# 150227_AriloTX_REV2_4_0_868MHZ.net
KiCad netlist of a schematic drawn in EAGLE
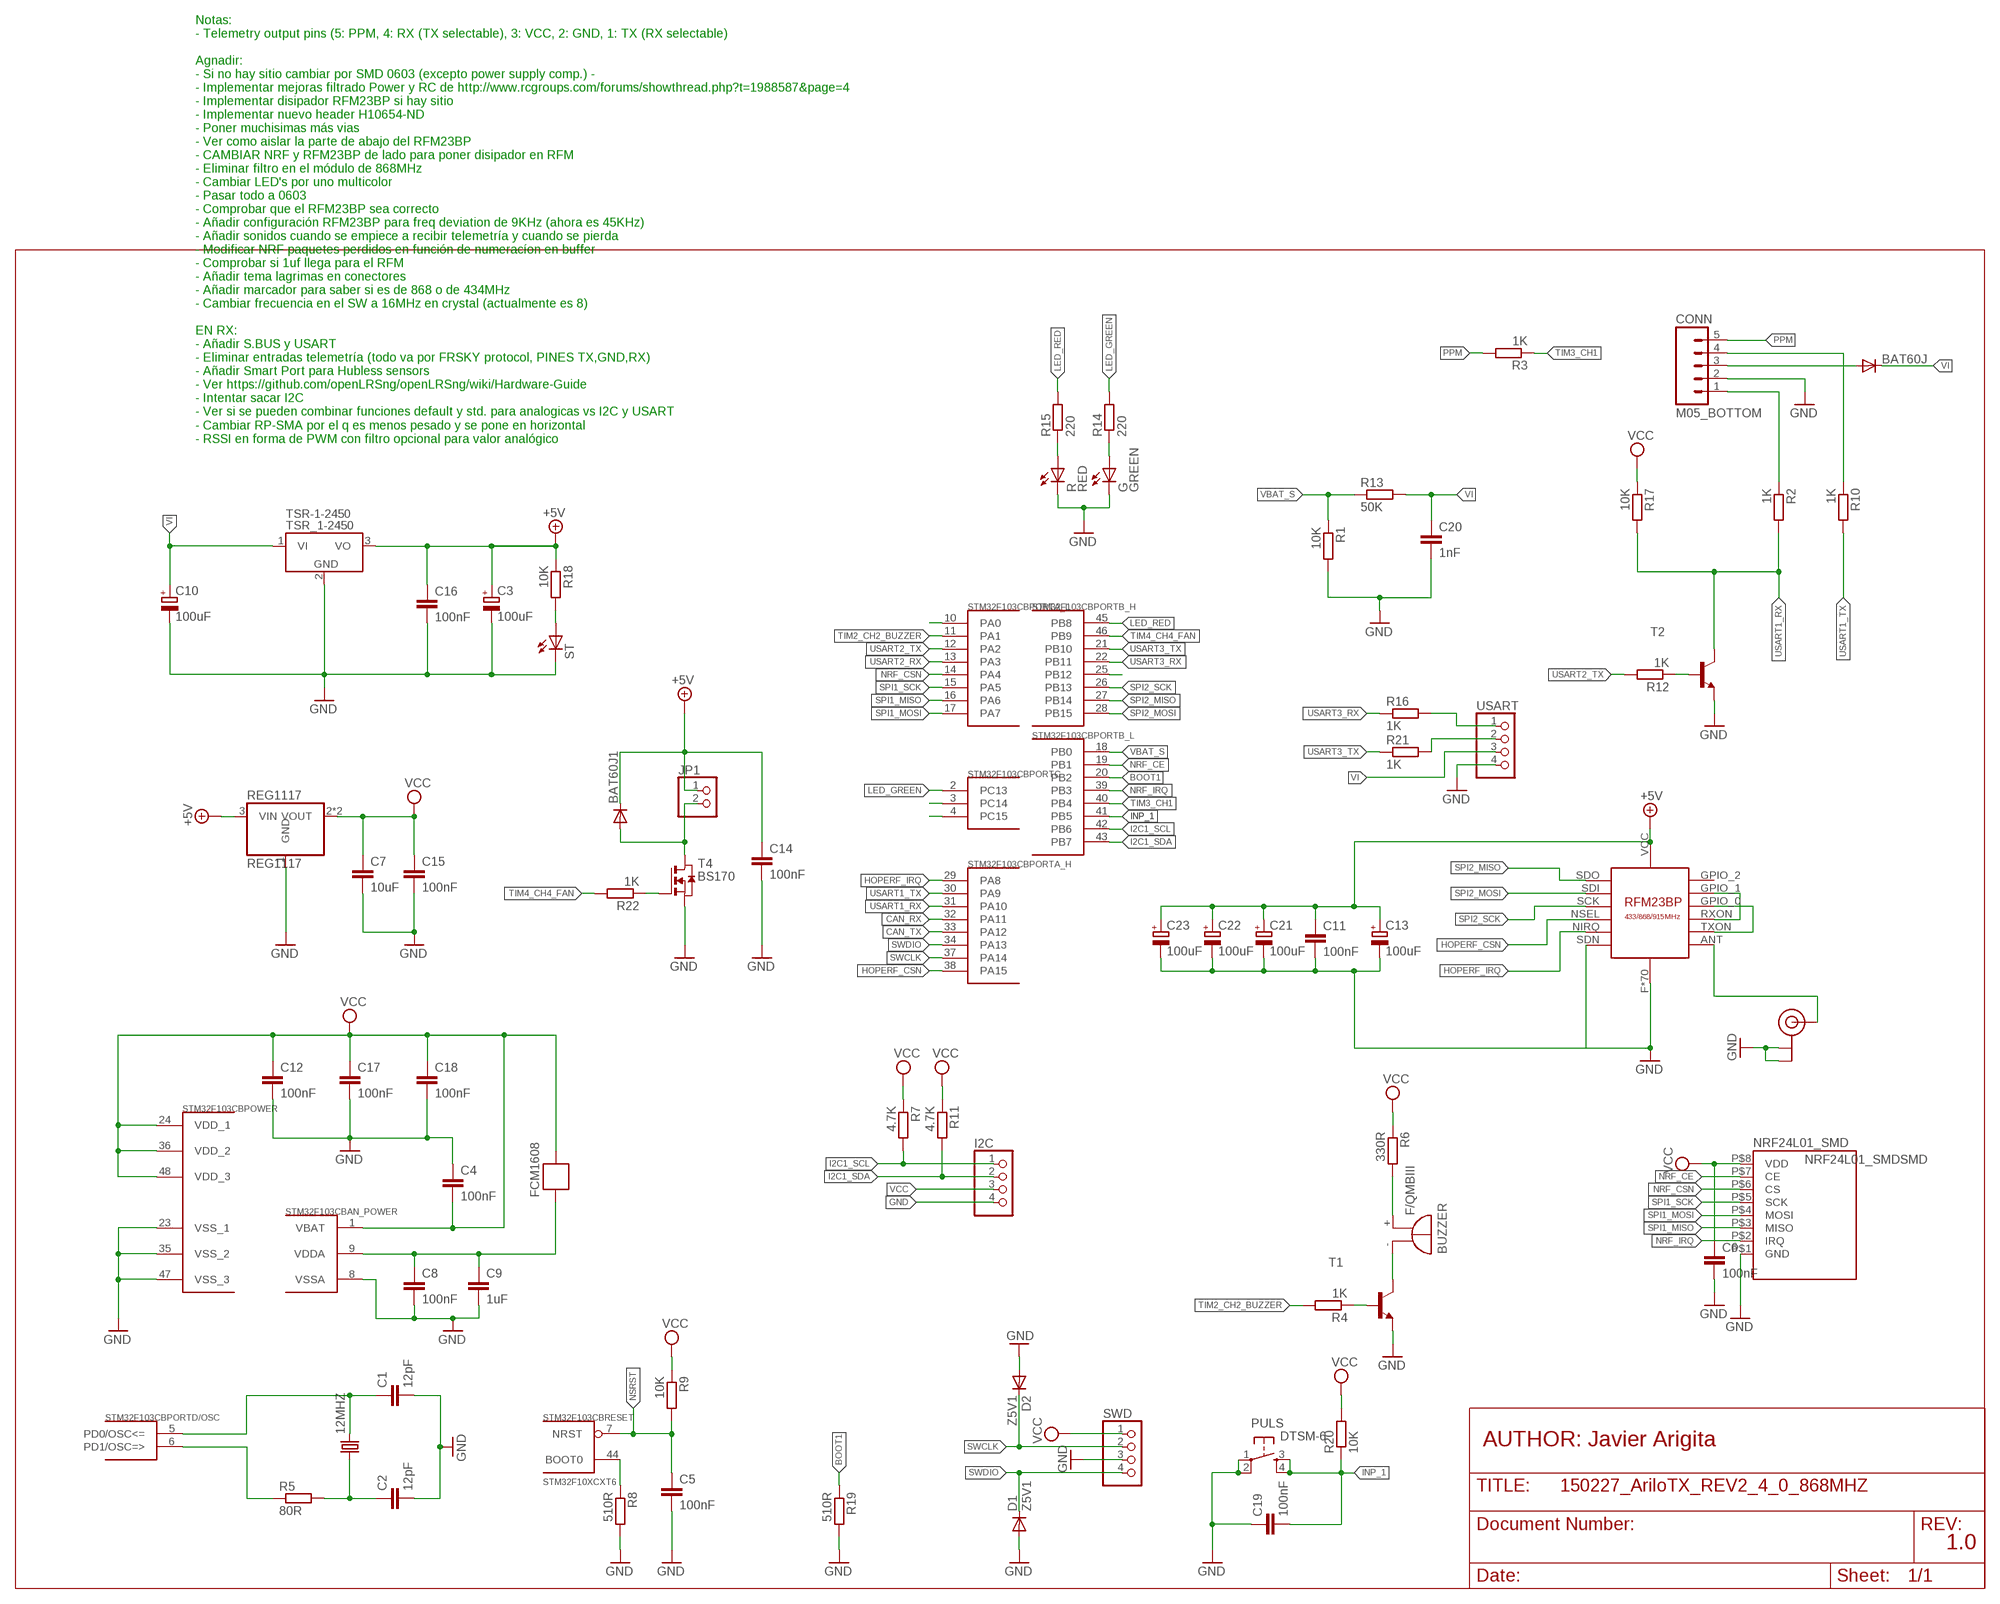
[diagram p0: schematic, sheet 1]

(export (version "E")
  (design (tool "Eeschema 10.0.6"))
  (components
    (comp (ref "12MHZ")
      (value "CRYSTAL5X3")
      (footprint "eagle-import:CRYSTAL-SMD-5X3")
      (libsource (lib "eagle-import") (part "CRYSTAL5X3"))
    )
    (comp (ref "BAT60J")
      (value "DIODE-SOD323-R")
      (footprint "eagle-import:SOD323-R")
      (libsource (lib "eagle-import") (part "DIODE-SOD323-R"))
    )
    (comp (ref "BAT60J1")
      (value "DIODE-SOD323-R")
      (footprint "eagle-import:SOD323-R")
      (libsource (lib "eagle-import") (part "DIODE-SOD323-R"))
    )
    (comp (ref "BUZZER")
      (value "F/QMBIII")
      (footprint "eagle-import:F_QMBIII")
      (libsource (lib "eagle-import") (part "F/QMBIII"))
    )
    (comp (ref "C1")
      (value "12pF")
      (footprint "eagle-import:C0603")
      (libsource (lib "eagle-import") (part "C-EUC0603"))
    )
    (comp (ref "C2")
      (value "12pF")
      (footprint "eagle-import:C0603")
      (libsource (lib "eagle-import") (part "C-EUC0603"))
    )
    (comp (ref "C3")
      (value "100uF")
      (footprint "eagle-import:SMC_B")
      (libsource (lib "eagle-import") (part "CPOL-EUSMCB"))
    )
    (comp (ref "C4")
      (value "100nF")
      (footprint "eagle-import:C0603")
      (libsource (lib "eagle-import") (part "C-EUC0603"))
    )
    (comp (ref "C5")
      (value "100nF")
      (footprint "eagle-import:C0603")
      (libsource (lib "eagle-import") (part "C-EUC0603"))
    )
    (comp (ref "C6")
      (value "100nF")
      (footprint "eagle-import:C0603")
      (libsource (lib "eagle-import") (part "C-EUC0603"))
    )
    (comp (ref "C7")
      (value "10uF")
      (footprint "eagle-import:C0805")
      (libsource (lib "eagle-import") (part "C-EUC0805"))
    )
    (comp (ref "C8")
      (value "100nF")
      (footprint "eagle-import:C0603")
      (libsource (lib "eagle-import") (part "C-EUC0603"))
    )
    (comp (ref "C9")
      (value "1uF")
      (footprint "eagle-import:C0603")
      (libsource (lib "eagle-import") (part "C-EUC0603"))
    )
    (comp (ref "C10")
      (value "100uF")
      (footprint "eagle-import:SMC_B")
      (libsource (lib "eagle-import") (part "CPOL-EUSMCB"))
    )
    (comp (ref "C11")
      (value "100nF")
      (footprint "eagle-import:C0603")
      (libsource (lib "eagle-import") (part "C-EUC0603"))
    )
    (comp (ref "C12")
      (value "100nF")
      (footprint "eagle-import:C0603")
      (libsource (lib "eagle-import") (part "C-EUC0603"))
    )
    (comp (ref "C13")
      (value "100uF")
      (footprint "eagle-import:SMC_B")
      (libsource (lib "eagle-import") (part "CPOL-EUSMCB"))
    )
    (comp (ref "C14")
      (value "100nF")
      (footprint "eagle-import:C0603")
      (libsource (lib "eagle-import") (part "C-EUC0603"))
    )
    (comp (ref "C15")
      (value "100nF")
      (footprint "eagle-import:C0603")
      (libsource (lib "eagle-import") (part "C-EUC0603"))
    )
    (comp (ref "C16")
      (value "100nF")
      (footprint "eagle-import:C0603")
      (libsource (lib "eagle-import") (part "C-EUC0603"))
    )
    (comp (ref "C17")
      (value "100nF")
      (footprint "eagle-import:C0603")
      (libsource (lib "eagle-import") (part "C-EUC0603"))
    )
    (comp (ref "C18")
      (value "100nF")
      (footprint "eagle-import:C0603")
      (libsource (lib "eagle-import") (part "C-EUC0603"))
    )
    (comp (ref "C19")
      (value "100nF")
      (footprint "eagle-import:C0603")
      (libsource (lib "eagle-import") (part "C-EUC0603"))
    )
    (comp (ref "C20")
      (value "1nF")
      (footprint "eagle-import:C0603")
      (libsource (lib "eagle-import") (part "C-EUC0603"))
    )
    (comp (ref "C21")
      (value "100uF")
      (footprint "eagle-import:SMC_B")
      (libsource (lib "eagle-import") (part "CPOL-EUSMCB"))
    )
    (comp (ref "C22")
      (value "100uF")
      (footprint "eagle-import:SMC_B")
      (libsource (lib "eagle-import") (part "CPOL-EUSMCB"))
    )
    (comp (ref "C23")
      (value "100uF")
      (footprint "eagle-import:SMC_B")
      (libsource (lib "eagle-import") (part "CPOL-EUSMCB"))
    )
    (comp (ref "CONN")
      (value "M05_BOTTOM")
      (footprint "eagle-import:M05_BOTTOM")
      (libsource (lib "eagle-import") (part "M05_BOTTOM"))
    )
    (comp (ref "D1")
      (value "Z5V1")
      (footprint "eagle-import:SOD323-R")
      (libsource (lib "eagle-import") (part "DIODE-SOD323-R"))
    )
    (comp (ref "D2")
      (value "Z5V1")
      (footprint "eagle-import:SOD323-R")
      (libsource (lib "eagle-import") (part "DIODE-SOD323-R"))
    )
    (comp (ref "FCM1608")
      (value "FERRITE-BEAD")
      (footprint "eagle-import:R0603")
      (libsource (lib "eagle-import") (part "FERRITE-BEAD"))
    )
    (comp (ref "G")
      (value "GREEN")
      (footprint "eagle-import:CHIP-LED0603")
      (libsource (lib "eagle-import") (part "LEDCHIP-LED0603"))
    )
    (comp (ref "I2C")
      (value "PINHD-1X4")
      (footprint "eagle-import:1X04")
      (libsource (lib "eagle-import") (part "PINHD-1X4"))
    )
    (comp (ref "JP1")
      (value "PINHD-1X2")
      (footprint "eagle-import:1X02")
      (libsource (lib "eagle-import") (part "PINHD-1X2"))
    )
    (comp (ref "NRF24L01_SMD")
      (value "NRF24L01_SMDSMD")
      (footprint "eagle-import:NRF24L01_SMD")
      (libsource (lib "eagle-import") (part "NRF24L01_SMDSMD"))
    )
    (comp (ref "PULS")
      (value "DTSM-6")
      (footprint "eagle-import:DTSM-6")
      (libsource (lib "eagle-import") (part "DTSM-6"))
    )
    (comp (ref "R")
      (value "RED")
      (footprint "eagle-import:CHIP-LED0603")
      (libsource (lib "eagle-import") (part "LEDCHIP-LED0603"))
    )
    (comp (ref "R1")
      (value "10K")
      (footprint "eagle-import:R0603")
      (libsource (lib "eagle-import") (part "R-EU_R0603"))
    )
    (comp (ref "R2")
      (value "1K")
      (footprint "eagle-import:R0603")
      (libsource (lib "eagle-import") (part "R-EU_R0603"))
    )
    (comp (ref "R3")
      (value "1K")
      (footprint "eagle-import:R0603")
      (libsource (lib "eagle-import") (part "R-EU_R0603"))
    )
    (comp (ref "R4")
      (value "1K")
      (footprint "eagle-import:R0603")
      (libsource (lib "eagle-import") (part "R-EU_R0603"))
    )
    (comp (ref "R5")
      (value "80R")
      (footprint "eagle-import:R0603")
      (libsource (lib "eagle-import") (part "R-EU_R0603"))
    )
    (comp (ref "R6")
      (value "330R")
      (footprint "eagle-import:R0603")
      (libsource (lib "eagle-import") (part "R-EU_R0603"))
    )
    (comp (ref "R7")
      (value "4.7K")
      (footprint "eagle-import:R0603")
      (libsource (lib "eagle-import") (part "R-EU_R0603"))
    )
    (comp (ref "R8")
      (value "510R")
      (footprint "eagle-import:R0603")
      (libsource (lib "eagle-import") (part "R-EU_R0603"))
    )
    (comp (ref "R9")
      (value "10K")
      (footprint "eagle-import:R0603")
      (libsource (lib "eagle-import") (part "R-EU_R0603"))
    )
    (comp (ref "R10")
      (value "1K")
      (footprint "eagle-import:R0603")
      (libsource (lib "eagle-import") (part "R-EU_R0603"))
    )
    (comp (ref "R11")
      (value "4.7K")
      (footprint "eagle-import:R0603")
      (libsource (lib "eagle-import") (part "R-EU_R0603"))
    )
    (comp (ref "R12")
      (value "1K")
      (footprint "eagle-import:R0603")
      (libsource (lib "eagle-import") (part "R-EU_R0603"))
    )
    (comp (ref "R13")
      (value "50K")
      (footprint "eagle-import:R0603")
      (libsource (lib "eagle-import") (part "R-EU_R0603"))
    )
    (comp (ref "R14")
      (value "220")
      (footprint "eagle-import:R0603")
      (libsource (lib "eagle-import") (part "R-EU_R0603"))
    )
    (comp (ref "R15")
      (value "220")
      (footprint "eagle-import:R0603")
      (libsource (lib "eagle-import") (part "R-EU_R0603"))
    )
    (comp (ref "R16")
      (value "1K")
      (footprint "eagle-import:R0603")
      (libsource (lib "eagle-import") (part "R-EU_R0603"))
    )
    (comp (ref "R17")
      (value "10K")
      (footprint "eagle-import:R0603")
      (libsource (lib "eagle-import") (part "R-EU_R0603"))
    )
    (comp (ref "R18")
      (value "10K")
      (footprint "eagle-import:R0603")
      (libsource (lib "eagle-import") (part "R-EU_R0603"))
    )
    (comp (ref "R19")
      (value "510R")
      (footprint "eagle-import:R0603")
      (libsource (lib "eagle-import") (part "R-EU_R0603"))
    )
    (comp (ref "R20")
      (value "10K")
      (footprint "eagle-import:R0603")
      (libsource (lib "eagle-import") (part "R-EU_R0603"))
    )
    (comp (ref "R21")
      (value "1K")
      (footprint "eagle-import:R0603")
      (libsource (lib "eagle-import") (part "R-EU_R0603"))
    )
    (comp (ref "R22")
      (value "1K")
      (footprint "eagle-import:R0603")
      (libsource (lib "eagle-import") (part "R-EU_R0603"))
    )
    (comp (ref "REG1117")
      (value "REG1117")
      (footprint "eagle-import:SOT223")
      (libsource (lib "eagle-import") (part "REG1117"))
    )
    (comp (ref "ST")
      (value "LEDCHIP-LED0603")
      (footprint "eagle-import:CHIP-LED0603")
      (libsource (lib "eagle-import") (part "LEDCHIP-LED0603"))
    )
    (comp (ref "STM32F103CB")
      (value "STM32F10XCXT6")
      (footprint "eagle-import:TQFP48")
      (libsource (lib "eagle-import") (part "STM32F10XCXT6"))
    )
    (comp (ref "SWD")
      (value "PINHD-1X4")
      (footprint "eagle-import:1X04")
      (libsource (lib "eagle-import") (part "PINHD-1X4"))
    )
    (comp (ref "T1")
      (value "BC848-NPN-SOT23-BEC")
      (footprint "eagle-import:SOT23-BEC")
      (libsource (lib "eagle-import") (part "-NPN-SOT23-BECBC848"))
    )
    (comp (ref "T2")
      (value "BC848-NPN-SOT23-BEC")
      (footprint "eagle-import:SOT23-BEC")
      (libsource (lib "eagle-import") (part "-NPN-SOT23-BECBC848"))
    )
    (comp (ref "T4")
      (value "BS170")
      (footprint "eagle-import:SOT-23")
      (libsource (lib "eagle-import") (part "NMOSSOT23"))
    )
    (comp (ref "TSR-1-2450")
      (value "TSR_1-2450")
      (footprint "eagle-import:TSR-1")
      (libsource (lib "eagle-import") (part "TSR_1-2450"))
    )
    (comp (ref "U$1")
      (value "RFM23BP")
      (footprint "eagle-import:RFM23BP")
      (libsource (lib "eagle-import") (part "RFM23BP"))
    )
    (comp (ref "U.FL")
      (value "U.FL")
      (footprint "eagle-import:U.FL")
      (libsource (lib "eagle-import") (part "U.FL"))
    )
    (comp (ref "USART")
      (value "PINHD-1X4")
      (footprint "eagle-import:1X04")
      (libsource (lib "eagle-import") (part "PINHD-1X4"))
    )
  )
  (nets
    (net (code "1") (name "+5V") (class "Default")
      (node (ref "BAT60J1") (pin "C") (pinfunction "C_C") (pintype "passive"))
      (node (ref "C11") (pin "1") (pinfunction "1_1") (pintype "passive"))
      (node (ref "C13") (pin "+") (pinfunction "+_+") (pintype "passive"))
      (node (ref "C14") (pin "1") (pinfunction "1_1") (pintype "passive"))
      (node (ref "C16") (pin "1") (pinfunction "1_1") (pintype "passive"))
      (node (ref "C21") (pin "+") (pinfunction "+_+") (pintype "passive"))
      (node (ref "C22") (pin "+") (pinfunction "+_+") (pintype "passive"))
      (node (ref "C23") (pin "+") (pinfunction "+_+") (pintype "passive"))
      (node (ref "C3") (pin "+") (pinfunction "+_+") (pintype "passive"))
      (node (ref "JP1") (pin "1") (pinfunction "1_1") (pintype "passive"))
      (node (ref "R18") (pin "1") (pinfunction "1_1") (pintype "passive"))
      (node (ref "REG1117") (pin "3") (pinfunction "VIN_3") (pintype "input"))
      (node (ref "TSR-1-2450") (pin "3") (pinfunction "VO_3") (pintype "power_in"))
      (node (ref "U$1") (pin "VCC") (pinfunction "VCC_VCC") (pintype "power_in"))
    )
    (net (code "2") (name "BOOT1") (class "Default")
      (node (ref "R19") (pin "1") (pinfunction "1_1") (pintype "passive"))
      (node (ref "STM32F103CB") (pin "20") (pinfunction "PB2_20") (pintype "bidirectional"))
    )
    (net (code "3") (name "CAN_RX") (class "Default")
      (node (ref "STM32F103CB") (pin "32") (pinfunction "PA11_32") (pintype "bidirectional"))
    )
    (net (code "4") (name "CAN_TX") (class "Default")
      (node (ref "STM32F103CB") (pin "33") (pinfunction "PA12_33") (pintype "bidirectional"))
    )
    (net (code "5") (name "GND") (class "Default")
      (node (ref "C1") (pin "2") (pinfunction "2_2") (pintype "passive"))
      (node (ref "C10") (pin "-") (pinfunction "-_-") (pintype "passive"))
      (node (ref "C11") (pin "2") (pinfunction "2_2") (pintype "passive"))
      (node (ref "C12") (pin "2") (pinfunction "2_2") (pintype "passive"))
      (node (ref "C13") (pin "-") (pinfunction "-_-") (pintype "passive"))
      (node (ref "C14") (pin "2") (pinfunction "2_2") (pintype "passive"))
      (node (ref "C15") (pin "2") (pinfunction "2_2") (pintype "passive"))
      (node (ref "C16") (pin "2") (pinfunction "2_2") (pintype "passive"))
      (node (ref "C17") (pin "2") (pinfunction "2_2") (pintype "passive"))
      (node (ref "C18") (pin "2") (pinfunction "2_2") (pintype "passive"))
      (node (ref "C19") (pin "1") (pinfunction "1_1") (pintype "passive"))
      (node (ref "C2") (pin "2") (pinfunction "2_2") (pintype "passive"))
      (node (ref "C20") (pin "2") (pinfunction "2_2") (pintype "passive"))
      (node (ref "C21") (pin "-") (pinfunction "-_-") (pintype "passive"))
      (node (ref "C22") (pin "-") (pinfunction "-_-") (pintype "passive"))
      (node (ref "C23") (pin "-") (pinfunction "-_-") (pintype "passive"))
      (node (ref "C3") (pin "-") (pinfunction "-_-") (pintype "passive"))
      (node (ref "C4") (pin "1") (pinfunction "1_1") (pintype "passive"))
      (node (ref "C5") (pin "2") (pinfunction "2_2") (pintype "passive"))
      (node (ref "C6") (pin "2") (pinfunction "2_2") (pintype "passive"))
      (node (ref "C7") (pin "2") (pinfunction "2_2") (pintype "passive"))
      (node (ref "C8") (pin "2") (pinfunction "2_2") (pintype "passive"))
      (node (ref "C9") (pin "2") (pinfunction "2_2") (pintype "passive"))
      (node (ref "CONN") (pin "2") (pinfunction "2_2") (pintype "passive"))
      (node (ref "D1") (pin "A") (pinfunction "A_A") (pintype "passive"))
      (node (ref "D2") (pin "A") (pinfunction "A_A") (pintype "passive"))
      (node (ref "G") (pin "C") (pinfunction "C_C") (pintype "passive"))
      (node (ref "I2C") (pin "4") (pinfunction "4_4") (pintype "passive"))
      (node (ref "NRF24L01_SMD") (pin "P$1") (pinfunction "GND_P$1") (pintype "power_in"))
      (node (ref "PULS") (pin "1") (pinfunction "1_1") (pintype "passive"))
      (node (ref "PULS") (pin "2") (pinfunction "2_2") (pintype "passive"))
      (node (ref "R") (pin "C") (pinfunction "C_C") (pintype "passive"))
      (node (ref "R1") (pin "2") (pinfunction "2_2") (pintype "passive"))
      (node (ref "R19") (pin "2") (pinfunction "2_2") (pintype "passive"))
      (node (ref "R8") (pin "2") (pinfunction "2_2") (pintype "passive"))
      (node (ref "REG1117") (pin "1") (pinfunction "GND_1") (pintype "power_in"))
      (node (ref "ST") (pin "C") (pinfunction "C_C") (pintype "passive"))
      (node (ref "STM32F103CB") (pin "23") (pinfunction "VSS_1_23") (pintype "power_in"))
      (node (ref "STM32F103CB") (pin "35") (pinfunction "VSS_2_35") (pintype "power_in"))
      (node (ref "STM32F103CB") (pin "47") (pinfunction "VSS_3_47") (pintype "power_in"))
      (node (ref "STM32F103CB") (pin "8") (pinfunction "VSSA_8") (pintype "power_in"))
      (node (ref "SWD") (pin "3") (pinfunction "3_3") (pintype "passive"))
      (node (ref "T1") (pin "E") (pinfunction "E_E") (pintype "passive"))
      (node (ref "T2") (pin "E") (pinfunction "E_E") (pintype "passive"))
      (node (ref "T4") (pin "2") (pinfunction "S_2") (pintype "passive"))
      (node (ref "TSR-1-2450") (pin "2") (pinfunction "GND_2") (pintype "power_in"))
      (node (ref "U$1") (pin "F") (pinfunction "GND_F") (pintype "power_in"))
      (node (ref "U$1") (pin "F1") (pinfunction "GND_F1") (pintype "power_in"))
      (node (ref "U$1") (pin "F10") (pinfunction "GND_F10") (pintype "power_in"))
      (node (ref "U$1") (pin "F11") (pinfunction "GND_F11") (pintype "power_in"))
      (node (ref "U$1") (pin "F12") (pinfunction "GND_F12") (pintype "power_in"))
      (node (ref "U$1") (pin "F13") (pinfunction "GND_F13") (pintype "power_in"))
      (node (ref "U$1") (pin "F14") (pinfunction "GND_F14") (pintype "power_in"))
      (node (ref "U$1") (pin "F15") (pinfunction "GND_F15") (pintype "power_in"))
      (node (ref "U$1") (pin "F16") (pinfunction "GND_F16") (pintype "power_in"))
      (node (ref "U$1") (pin "F17") (pinfunction "GND_F17") (pintype "power_in"))
      (node (ref "U$1") (pin "F18") (pinfunction "GND_F18") (pintype "power_in"))
      (node (ref "U$1") (pin "F19") (pinfunction "GND_F19") (pintype "power_in"))
      (node (ref "U$1") (pin "F2") (pinfunction "GND_F2") (pintype "power_in"))
      (node (ref "U$1") (pin "F20") (pinfunction "GND_F20") (pintype "power_in"))
      (node (ref "U$1") (pin "F21") (pinfunction "GND_F21") (pintype "power_in"))
      (node (ref "U$1") (pin "F22") (pinfunction "GND_F22") (pintype "power_in"))
      (node (ref "U$1") (pin "F23") (pinfunction "GND_F23") (pintype "power_in"))
      (node (ref "U$1") (pin "F24") (pinfunction "GND_F24") (pintype "power_in"))
      (node (ref "U$1") (pin "F25") (pinfunction "GND_F25") (pintype "power_in"))
      (node (ref "U$1") (pin "F26") (pinfunction "GND_F26") (pintype "power_in"))
      (node (ref "U$1") (pin "F27") (pinfunction "GND_F27") (pintype "power_in"))
      (node (ref "U$1") (pin "F28") (pinfunction "GND_F28") (pintype "power_in"))
      (node (ref "U$1") (pin "F29") (pinfunction "GND_F29") (pintype "power_in"))
      (node (ref "U$1") (pin "F3") (pinfunction "GND_F3") (pintype "power_in"))
      (node (ref "U$1") (pin "F30") (pinfunction "GND_F30") (pintype "power_in"))
      (node (ref "U$1") (pin "F31") (pinfunction "GND_F31") (pintype "power_in"))
      (node (ref "U$1") (pin "F32") (pinfunction "GND_F32") (pintype "power_in"))
      (node (ref "U$1") (pin "F33") (pinfunction "GND_F33") (pintype "power_in"))
      (node (ref "U$1") (pin "F34") (pinfunction "GND_F34") (pintype "power_in"))
      (node (ref "U$1") (pin "F35") (pinfunction "GND_F35") (pintype "power_in"))
      (node (ref "U$1") (pin "F36") (pinfunction "GND_F36") (pintype "power_in"))
      (node (ref "U$1") (pin "F37") (pinfunction "GND_F37") (pintype "power_in"))
      (node (ref "U$1") (pin "F38") (pinfunction "GND_F38") (pintype "power_in"))
      (node (ref "U$1") (pin "F39") (pinfunction "GND_F39") (pintype "power_in"))
      (node (ref "U$1") (pin "F4") (pinfunction "GND_F4") (pintype "power_in"))
      (node (ref "U$1") (pin "F40") (pinfunction "GND_F40") (pintype "power_in"))
      (node (ref "U$1") (pin "F41") (pinfunction "GND_F41") (pintype "power_in"))
      (node (ref "U$1") (pin "F42") (pinfunction "GND_F42") (pintype "power_in"))
      (node (ref "U$1") (pin "F43") (pinfunction "GND_F43") (pintype "power_in"))
      (node (ref "U$1") (pin "F44") (pinfunction "GND_F44") (pintype "power_in"))
      (node (ref "U$1") (pin "F45") (pinfunction "GND_F45") (pintype "power_in"))
      (node (ref "U$1") (pin "F46") (pinfunction "GND_F46") (pintype "power_in"))
      (node (ref "U$1") (pin "F47") (pinfunction "GND_F47") (pintype "power_in"))
      (node (ref "U$1") (pin "F48") (pinfunction "GND_F48") (pintype "power_in"))
      (node (ref "U$1") (pin "F49") (pinfunction "GND_F49") (pintype "power_in"))
      (node (ref "U$1") (pin "F5") (pinfunction "GND_F5") (pintype "power_in"))
      (node (ref "U$1") (pin "F50") (pinfunction "GND_F50") (pintype "power_in"))
      (node (ref "U$1") (pin "F51") (pinfunction "GND_F51") (pintype "power_in"))
      (node (ref "U$1") (pin "F52") (pinfunction "GND_F52") (pintype "power_in"))
      (node (ref "U$1") (pin "F53") (pinfunction "GND_F53") (pintype "power_in"))
      (node (ref "U$1") (pin "F54") (pinfunction "GND_F54") (pintype "power_in"))
      (node (ref "U$1") (pin "F55") (pinfunction "GND_F55") (pintype "power_in"))
      (node (ref "U$1") (pin "F56") (pinfunction "GND_F56") (pintype "power_in"))
      (node (ref "U$1") (pin "F57") (pinfunction "GND_F57") (pintype "power_in"))
      (node (ref "U$1") (pin "F58") (pinfunction "GND_F58") (pintype "power_in"))
      (node (ref "U$1") (pin "F59") (pinfunction "GND_F59") (pintype "power_in"))
      (node (ref "U$1") (pin "F6") (pinfunction "GND_F6") (pintype "power_in"))
      (node (ref "U$1") (pin "F60") (pinfunction "GND_F60") (pintype "power_in"))
      (node (ref "U$1") (pin "F61") (pinfunction "GND_F61") (pintype "power_in"))
      (node (ref "U$1") (pin "F62") (pinfunction "GND_F62") (pintype "power_in"))
      (node (ref "U$1") (pin "F63") (pinfunction "GND_F63") (pintype "power_in"))
      (node (ref "U$1") (pin "F64") (pinfunction "GND_F64") (pintype "power_in"))
      (node (ref "U$1") (pin "F65") (pinfunction "GND_F65") (pintype "power_in"))
      (node (ref "U$1") (pin "F7") (pinfunction "GND_F7") (pintype "power_in"))
      (node (ref "U$1") (pin "F8") (pinfunction "GND_F8") (pintype "power_in"))
      (node (ref "U$1") (pin "F9") (pinfunction "GND_F9") (pintype "power_in"))
      (node (ref "U$1") (pin "GND1") (pinfunction "GND_GND1") (pintype "power_in"))
      (node (ref "U$1") (pin "GND2") (pinfunction "GND_GND2") (pintype "power_in"))
      (node (ref "U$1") (pin "GND3") (pinfunction "GND_GND3") (pintype "power_in"))
      (node (ref "U$1") (pin "GND_HEAT") (pinfunction "GND_GND_HEAT") (pintype "power_in"))
      (node (ref "U$1") (pin "SDN") (pinfunction "SDN_SDN") (pintype "bidirectional"))
      (node (ref "U.FL") (pin "P$1") (pinfunction "GND_P$1") (pintype "bidirectional"))
      (node (ref "U.FL") (pin "P$2") (pinfunction "GND_P$2") (pintype "bidirectional"))
      (node (ref "USART") (pin "4") (pinfunction "4_4") (pintype "passive"))
    )
    (net (code "6") (name "HOPERF_CSN") (class "Default")
      (node (ref "STM32F103CB") (pin "38") (pinfunction "PA15_38") (pintype "bidirectional"))
      (node (ref "U$1") (pin "NSEL") (pinfunction "NSEL_NSEL") (pintype "bidirectional"))
    )
    (net (code "7") (name "HOPERF_IRQ") (class "Default")
      (node (ref "STM32F103CB") (pin "29") (pinfunction "PA8_29") (pintype "bidirectional"))
      (node (ref "U$1") (pin "NIRQ") (pinfunction "NIRQ_NIRQ") (pintype "bidirectional"))
    )
    (net (code "8") (name "I2C1_SCL") (class "Default")
      (node (ref "I2C") (pin "1") (pinfunction "1_1") (pintype "passive"))
      (node (ref "R7") (pin "2") (pinfunction "2_2") (pintype "passive"))
      (node (ref "STM32F103CB") (pin "42") (pinfunction "PB6_42") (pintype "bidirectional"))
    )
    (net (code "9") (name "I2C1_SDA") (class "Default")
      (node (ref "I2C") (pin "2") (pinfunction "2_2") (pintype "passive"))
      (node (ref "R11") (pin "2") (pinfunction "2_2") (pintype "passive"))
      (node (ref "STM32F103CB") (pin "43") (pinfunction "PB7_43") (pintype "bidirectional"))
    )
    (net (code "10") (name "INP_1") (class "Default")
      (node (ref "C19") (pin "2") (pinfunction "2_2") (pintype "passive"))
      (node (ref "PULS") (pin "3") (pinfunction "3_3") (pintype "passive"))
      (node (ref "PULS") (pin "4") (pinfunction "4_4") (pintype "passive"))
      (node (ref "R20") (pin "1") (pinfunction "1_1") (pintype "passive"))
      (node (ref "STM32F103CB") (pin "41") (pinfunction "PB5_41") (pintype "bidirectional"))
    )
    (net (code "11") (name "LED_GREEN") (class "Default")
      (node (ref "R14") (pin "2") (pinfunction "2_2") (pintype "passive"))
      (node (ref "STM32F103CB") (pin "2") (pinfunction "PC13_2") (pintype "bidirectional"))
    )
    (net (code "12") (name "LED_RED") (class "Default")
      (node (ref "R15") (pin "2") (pinfunction "2_2") (pintype "passive"))
      (node (ref "STM32F103CB") (pin "45") (pinfunction "PB8_45") (pintype "bidirectional"))
    )
    (net (code "13") (name "NRF_CE") (class "Default")
      (node (ref "NRF24L01_SMD") (pin "P$7") (pinfunction "CE_P$7") (pintype "input"))
      (node (ref "STM32F103CB") (pin "19") (pinfunction "PB1_19") (pintype "bidirectional"))
    )
    (net (code "14") (name "NRF_CSN") (class "Default")
      (node (ref "NRF24L01_SMD") (pin "P$6") (pinfunction "CS_P$6") (pintype "input"))
      (node (ref "STM32F103CB") (pin "14") (pinfunction "PA4_14") (pintype "bidirectional"))
    )
    (net (code "15") (name "NRF_IRQ") (class "Default")
      (node (ref "NRF24L01_SMD") (pin "P$2") (pinfunction "IRQ_P$2") (pintype "output"))
      (node (ref "STM32F103CB") (pin "39") (pinfunction "PB3_39") (pintype "bidirectional"))
    )
    (net (code "16") (name "NSRST") (class "Default")
      (node (ref "C5") (pin "1") (pinfunction "1_1") (pintype "passive"))
      (node (ref "R9") (pin "2") (pinfunction "2_2") (pintype "passive"))
      (node (ref "STM32F103CB") (pin "7") (pinfunction "NRST_7") (pintype "input"))
    )
    (net (code "17") (name "Net-(12MHZ-2)") (class "Default")
      (node (ref "12MHZ") (pin "3") (pinfunction "2_3") (pintype "passive"))
      (node (ref "C1") (pin "1") (pinfunction "1_1") (pintype "passive"))
      (node (ref "STM32F103CB") (pin "5") (pinfunction "PD0/OSC<=_5") (pintype "bidirectional"))
    )
    (net (code "18") (name "Net-(12MHZ-Pad1)") (class "Default")
      (node (ref "12MHZ") (pin "1") (pinfunction "1_1") (pintype "passive"))
      (node (ref "C2") (pin "1") (pinfunction "1_1") (pintype "passive"))
      (node (ref "R5") (pin "2") (pinfunction "2_2") (pintype "passive"))
    )
    (net (code "19") (name "Net-(BAT60J-PadA)") (class "Default")
      (node (ref "BAT60J") (pin "A") (pinfunction "A_A") (pintype "passive"))
      (node (ref "CONN") (pin "3") (pinfunction "3_3") (pintype "passive"))
    )
    (net (code "20") (name "Net-(BUZZER-+)") (class "Default")
      (node (ref "BUZZER") (pin "-") (pinfunction "+_-") (pintype "passive"))
      (node (ref "T1") (pin "C") (pinfunction "C_C") (pintype "passive"))
    )
    (net (code "21") (name "Net-(BUZZER--)") (class "Default")
      (node (ref "BUZZER") (pin "+") (pinfunction "-_+") (pintype "passive"))
      (node (ref "R6") (pin "2") (pinfunction "2_2") (pintype "passive"))
    )
    (net (code "22") (name "Net-(CONN-Pad1)") (class "Default")
      (node (ref "CONN") (pin "1") (pinfunction "1_1") (pintype "passive"))
      (node (ref "R2") (pin "1") (pinfunction "1_1") (pintype "passive"))
    )
    (net (code "23") (name "Net-(CONN-Pad4)") (class "Default")
      (node (ref "CONN") (pin "4") (pinfunction "4_4") (pintype "passive"))
      (node (ref "R10") (pin "1") (pinfunction "1_1") (pintype "passive"))
    )
    (net (code "24") (name "Net-(FCM1608-P$2)") (class "Default")
      (node (ref "C8") (pin "1") (pinfunction "1_1") (pintype "passive"))
      (node (ref "C9") (pin "1") (pinfunction "1_1") (pintype "passive"))
      (node (ref "FCM1608") (pin "2") (pinfunction "P$2_2") (pintype "bidirectional"))
      (node (ref "STM32F103CB") (pin "9") (pinfunction "VDDA_9") (pintype "power_in"))
    )
    (net (code "25") (name "Net-(G-PadA)") (class "Default")
      (node (ref "G") (pin "A") (pinfunction "A_A") (pintype "passive"))
      (node (ref "R14") (pin "1") (pinfunction "1_1") (pintype "passive"))
    )
    (net (code "26") (name "Net-(R-PadA)") (class "Default")
      (node (ref "R") (pin "A") (pinfunction "A_A") (pintype "passive"))
      (node (ref "R15") (pin "1") (pinfunction "1_1") (pintype "passive"))
    )
    (net (code "27") (name "Net-(R4-Pad1)") (class "Default")
      (node (ref "R4") (pin "1") (pinfunction "1_1") (pintype "passive"))
      (node (ref "T1") (pin "B") (pinfunction "B_B") (pintype "passive"))
    )
    (net (code "28") (name "Net-(R12-Pad1)") (class "Default")
      (node (ref "R12") (pin "1") (pinfunction "1_1") (pintype "passive"))
      (node (ref "T2") (pin "B") (pinfunction "B_B") (pintype "passive"))
    )
    (net (code "29") (name "Net-(R16-Pad2)") (class "Default")
      (node (ref "R16") (pin "2") (pinfunction "2_2") (pintype "passive"))
      (node (ref "USART") (pin "1") (pinfunction "1_1") (pintype "passive"))
    )
    (net (code "30") (name "Net-(R18-Pad2)") (class "Default")
      (node (ref "R18") (pin "2") (pinfunction "2_2") (pintype "passive"))
      (node (ref "ST") (pin "A") (pinfunction "A_A") (pintype "passive"))
    )
    (net (code "31") (name "Net-(R21-Pad2)") (class "Default")
      (node (ref "R21") (pin "2") (pinfunction "2_2") (pintype "passive"))
      (node (ref "USART") (pin "2") (pinfunction "2_2") (pintype "passive"))
    )
    (net (code "32") (name "Net-(STM32F103CBG-PD1{slash}OSC=>)") (class "Default")
      (node (ref "R5") (pin "1") (pinfunction "1_1") (pintype "passive"))
      (node (ref "STM32F103CB") (pin "6") (pinfunction "PD1/OSC=>_6") (pintype "bidirectional"))
    )
    (net (code "33") (name "Net-(STM32F103CBI-BOOT0)") (class "Default")
      (node (ref "R8") (pin "1") (pinfunction "1_1") (pintype "passive"))
      (node (ref "STM32F103CB") (pin "44") (pinfunction "BOOT0_44") (pintype "input"))
    )
    (net (code "34") (name "Net-(T4-D)") (class "Default")
      (node (ref "BAT60J1") (pin "A") (pinfunction "A_A") (pintype "passive"))
      (node (ref "JP1") (pin "2") (pinfunction "2_2") (pintype "passive"))
      (node (ref "T4") (pin "1") (pinfunction "D_1") (pintype "passive"))
    )
    (net (code "35") (name "Net-(T4-G)") (class "Default")
      (node (ref "R22") (pin "1") (pinfunction "1_1") (pintype "passive"))
      (node (ref "T4") (pin "3") (pinfunction "G_3") (pintype "passive"))
    )
    (net (code "36") (name "Net-(U$1-PadGPIO_0)") (class "Default")
      (node (ref "U$1") (pin "GPIO_0") (pinfunction "GPIO_0_GPIO_0") (pintype "bidirectional"))
      (node (ref "U$1") (pin "TXON") (pinfunction "TXON_TXON") (pintype "bidirectional"))
    )
    (net (code "37") (name "Net-(U$1-PadGPIO_1)") (class "Default")
      (node (ref "U$1") (pin "GPIO_1") (pinfunction "GPIO_1_GPIO_1") (pintype "bidirectional"))
      (node (ref "U$1") (pin "RXON") (pinfunction "RXON_RXON") (pintype "bidirectional"))
    )
    (net (code "38") (name "Net-(U.FL-SIGNAL)") (class "Default")
      (node (ref "U$1") (pin "ANT") (pinfunction "ANT_ANT") (pintype "bidirectional"))
      (node (ref "U.FL") (pin "P$3") (pinfunction "SIGNAL_P$3") (pintype "bidirectional"))
    )
    (net (code "39") (name "PPM") (class "Default")
      (node (ref "CONN") (pin "5") (pinfunction "5_5") (pintype "passive"))
      (node (ref "R3") (pin "2") (pinfunction "2_2") (pintype "passive"))
    )
    (net (code "40") (name "SPI1_MISO") (class "Default")
      (node (ref "NRF24L01_SMD") (pin "P$3") (pinfunction "MISO_P$3") (pintype "output"))
      (node (ref "STM32F103CB") (pin "16") (pinfunction "PA6_16") (pintype "bidirectional"))
    )
    (net (code "41") (name "SPI1_MOSI") (class "Default")
      (node (ref "NRF24L01_SMD") (pin "P$4") (pinfunction "MOSI_P$4") (pintype "input"))
      (node (ref "STM32F103CB") (pin "17") (pinfunction "PA7_17") (pintype "bidirectional"))
    )
    (net (code "42") (name "SPI1_SCK") (class "Default")
      (node (ref "NRF24L01_SMD") (pin "P$5") (pinfunction "SCK_P$5") (pintype "input"))
      (node (ref "STM32F103CB") (pin "15") (pinfunction "PA5_15") (pintype "bidirectional"))
    )
    (net (code "43") (name "SPI2_MISO") (class "Default")
      (node (ref "STM32F103CB") (pin "27") (pinfunction "PB14_27") (pintype "bidirectional"))
      (node (ref "U$1") (pin "SDO") (pinfunction "SDO_SDO") (pintype "bidirectional"))
    )
    (net (code "44") (name "SPI2_MOSI") (class "Default")
      (node (ref "STM32F103CB") (pin "28") (pinfunction "PB15_28") (pintype "bidirectional"))
      (node (ref "U$1") (pin "SDI") (pinfunction "SDI_SDI") (pintype "bidirectional"))
    )
    (net (code "45") (name "SPI2_SCK") (class "Default")
      (node (ref "STM32F103CB") (pin "26") (pinfunction "PB13_26") (pintype "bidirectional"))
      (node (ref "U$1") (pin "SCK") (pinfunction "SCK_SCK") (pintype "bidirectional"))
    )
    (net (code "46") (name "SWCLK") (class "Default")
      (node (ref "D2") (pin "C") (pinfunction "C_C") (pintype "passive"))
      (node (ref "STM32F103CB") (pin "37") (pinfunction "PA14_37") (pintype "bidirectional"))
      (node (ref "SWD") (pin "2") (pinfunction "2_2") (pintype "passive"))
    )
    (net (code "47") (name "SWDIO") (class "Default")
      (node (ref "D1") (pin "C") (pinfunction "C_C") (pintype "passive"))
      (node (ref "STM32F103CB") (pin "34") (pinfunction "PA13_34") (pintype "bidirectional"))
      (node (ref "SWD") (pin "4") (pinfunction "4_4") (pintype "passive"))
    )
    (net (code "48") (name "TIM2_CH2_BUZZER") (class "Default")
      (node (ref "R4") (pin "2") (pinfunction "2_2") (pintype "passive"))
      (node (ref "STM32F103CB") (pin "11") (pinfunction "PA1_11") (pintype "bidirectional"))
    )
    (net (code "49") (name "TIM3_CH1") (class "Default")
      (node (ref "R3") (pin "1") (pinfunction "1_1") (pintype "passive"))
      (node (ref "STM32F103CB") (pin "40") (pinfunction "PB4_40") (pintype "bidirectional"))
    )
    (net (code "50") (name "TIM4_CH4_FAN") (class "Default")
      (node (ref "R22") (pin "2") (pinfunction "2_2") (pintype "passive"))
      (node (ref "STM32F103CB") (pin "46") (pinfunction "PB9_46") (pintype "bidirectional"))
    )
    (net (code "51") (name "USART1_RX") (class "Default")
      (node (ref "R17") (pin "2") (pinfunction "2_2") (pintype "passive"))
      (node (ref "R2") (pin "2") (pinfunction "2_2") (pintype "passive"))
      (node (ref "STM32F103CB") (pin "31") (pinfunction "PA10_31") (pintype "bidirectional"))
      (node (ref "T2") (pin "C") (pinfunction "C_C") (pintype "passive"))
    )
    (net (code "52") (name "USART1_TX") (class "Default")
      (node (ref "R10") (pin "2") (pinfunction "2_2") (pintype "passive"))
      (node (ref "STM32F103CB") (pin "30") (pinfunction "PA9_30") (pintype "bidirectional"))
    )
    (net (code "53") (name "USART2_RX") (class "Default")
      (node (ref "STM32F103CB") (pin "13") (pinfunction "PA3_13") (pintype "bidirectional"))
    )
    (net (code "54") (name "USART2_TX") (class "Default")
      (node (ref "R12") (pin "2") (pinfunction "2_2") (pintype "passive"))
      (node (ref "STM32F103CB") (pin "12") (pinfunction "PA2_12") (pintype "bidirectional"))
    )
    (net (code "55") (name "USART3_RX") (class "Default")
      (node (ref "R16") (pin "1") (pinfunction "1_1") (pintype "passive"))
      (node (ref "STM32F103CB") (pin "22") (pinfunction "PB11_22") (pintype "bidirectional"))
    )
    (net (code "56") (name "USART3_TX") (class "Default")
      (node (ref "R21") (pin "1") (pinfunction "1_1") (pintype "passive"))
      (node (ref "STM32F103CB") (pin "21") (pinfunction "PB10_21") (pintype "bidirectional"))
    )
    (net (code "57") (name "VBAT_S") (class "Default")
      (node (ref "R1") (pin "1") (pinfunction "1_1") (pintype "passive"))
      (node (ref "R13") (pin "1") (pinfunction "1_1") (pintype "passive"))
      (node (ref "STM32F103CB") (pin "18") (pinfunction "PB0_18") (pintype "bidirectional"))
    )
    (net (code "58") (name "VCC") (class "Default")
      (node (ref "C12") (pin "1") (pinfunction "1_1") (pintype "passive"))
      (node (ref "C15") (pin "1") (pinfunction "1_1") (pintype "passive"))
      (node (ref "C17") (pin "1") (pinfunction "1_1") (pintype "passive"))
      (node (ref "C18") (pin "1") (pinfunction "1_1") (pintype "passive"))
      (node (ref "C4") (pin "2") (pinfunction "2_2") (pintype "passive"))
      (node (ref "C6") (pin "1") (pinfunction "1_1") (pintype "passive"))
      (node (ref "C7") (pin "1") (pinfunction "1_1") (pintype "passive"))
      (node (ref "FCM1608") (pin "1") (pinfunction "P$1_1") (pintype "bidirectional"))
      (node (ref "I2C") (pin "3") (pinfunction "3_3") (pintype "passive"))
      (node (ref "NRF24L01_SMD") (pin "P$8") (pinfunction "VDD_P$8") (pintype "bidirectional"))
      (node (ref "R11") (pin "1") (pinfunction "1_1") (pintype "passive"))
      (node (ref "R17") (pin "1") (pinfunction "1_1") (pintype "passive"))
      (node (ref "R20") (pin "2") (pinfunction "2_2") (pintype "passive"))
      (node (ref "R6") (pin "1") (pinfunction "1_1") (pintype "passive"))
      (node (ref "R7") (pin "1") (pinfunction "1_1") (pintype "passive"))
      (node (ref "R9") (pin "1") (pinfunction "1_1") (pintype "passive"))
      (node (ref "REG1117") (pin "2") (pinfunction "VOUT_2") (pintype "power_in"))
      (node (ref "REG1117") (pin "4") (pinfunction "VOUT_4") (pintype "power_in"))
      (node (ref "STM32F103CB") (pin "1") (pinfunction "VBAT_1") (pintype "power_in"))
      (node (ref "STM32F103CB") (pin "24") (pinfunction "VDD_1_24") (pintype "power_in"))
      (node (ref "STM32F103CB") (pin "36") (pinfunction "VDD_2_36") (pintype "power_in"))
      (node (ref "STM32F103CB") (pin "48") (pinfunction "VDD_3_48") (pintype "power_in"))
      (node (ref "SWD") (pin "1") (pinfunction "1_1") (pintype "passive"))
    )
    (net (code "59") (name "VI") (class "Default")
      (node (ref "BAT60J") (pin "C") (pinfunction "C_C") (pintype "passive"))
      (node (ref "C10") (pin "+") (pinfunction "+_+") (pintype "passive"))
      (node (ref "C20") (pin "1") (pinfunction "1_1") (pintype "passive"))
      (node (ref "R13") (pin "2") (pinfunction "2_2") (pintype "passive"))
      (node (ref "TSR-1-2450") (pin "1") (pinfunction "VI_1") (pintype "power_in"))
      (node (ref "USART") (pin "3") (pinfunction "3_3") (pintype "passive"))
    )
    (net (code "60") (name "unconnected-(STM32F103CBC-PA0-Pad10)") (class "Default")
      (node (ref "STM32F103CB") (pin "10") (pinfunction "PA0_10") (pintype "bidirectional"))
    )
    (net (code "61") (name "unconnected-(STM32F103CBD-PB12-Pad25)") (class "Default")
      (node (ref "STM32F103CB") (pin "25") (pinfunction "PB12_25") (pintype "bidirectional"))
    )
    (net (code "62") (name "unconnected-(STM32F103CBF-PC14-Pad3)") (class "Default")
      (node (ref "STM32F103CB") (pin "3") (pinfunction "PC14_3") (pintype "bidirectional"))
    )
    (net (code "63") (name "unconnected-(STM32F103CBF-PC15-Pad4)") (class "Default")
      (node (ref "STM32F103CB") (pin "4") (pinfunction "PC15_4") (pintype "bidirectional"))
    )
    (net (code "64") (name "unconnected-(U$1-PadGPIO_2)") (class "Default")
      (node (ref "U$1") (pin "GPIO_2") (pinfunction "GPIO_2_GPIO_2") (pintype "bidirectional"))
    )
  )
)
